# Overview.net
KiCad netlist of a schematic drawn in Altium Designer
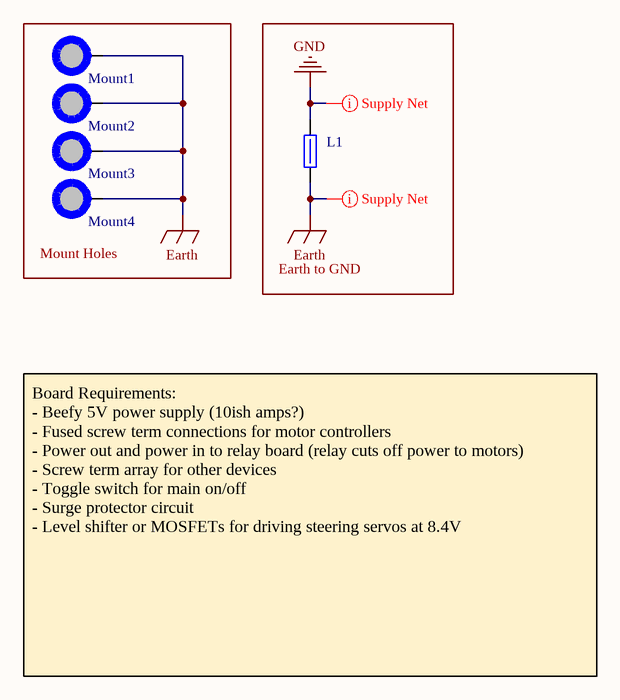
[diagram p0: Overview.SchDoc]

(export (version "E")
  (design (tool "Eeschema 10.0.6"))
  (components
    (comp (ref "L1")
      (value "742792040")
      (footprint "[Ferrite] SMD Bead 0805 (2)")
      (libsource (lib "RADM Components") (part "[Ferrite] SMD Ferrite Bead (2)"))
    )
    (comp (ref "Mount1")
      (value "M3 Mount Hole")
      (footprint "[Mount] M3 Mount Hole")
      (description "Place at least 4.5mm from board edge. Plated.")
      (libsource (lib "RADM Connectors") (part "[Mount] M3 Mount Hole"))
    )
    (comp (ref "Mount2")
      (value "M3 Mount Hole")
      (footprint "[Mount] M3 Mount Hole")
      (description "Place at least 4.5mm from board edge. Plated.")
      (libsource (lib "RADM Connectors") (part "[Mount] M3 Mount Hole"))
    )
    (comp (ref "Mount3")
      (value "M3 Mount Hole")
      (footprint "[Mount] M3 Mount Hole")
      (description "Place at least 4.5mm from board edge. Plated.")
      (libsource (lib "RADM Connectors") (part "[Mount] M3 Mount Hole"))
    )
    (comp (ref "Mount4")
      (value "M3 Mount Hole")
      (footprint "[Mount] M3 Mount Hole")
      (description "Place at least 4.5mm from board edge. Plated.")
      (libsource (lib "RADM Connectors") (part "[Mount] M3 Mount Hole"))
    )
  )
  (nets
    (net (code "1") (name "Earth") (class "Default")
      (node (ref "L1") (pin "1") (pinfunction "1_1") (pintype "passive"))
      (node (ref "Mount1") (pin "1") (pintype "power_in"))
      (node (ref "Mount2") (pin "1") (pintype "power_in"))
      (node (ref "Mount3") (pin "1") (pintype "power_in"))
      (node (ref "Mount4") (pin "1") (pintype "power_in"))
    )
    (net (code "2") (name "GND") (class "Default")
      (node (ref "L1") (pin "2") (pinfunction "2_2") (pintype "passive"))
    )
  )
)
